# PTFV_GECKO_PWR.net
KiCad netlist of a schematic drawn in Altium Designer
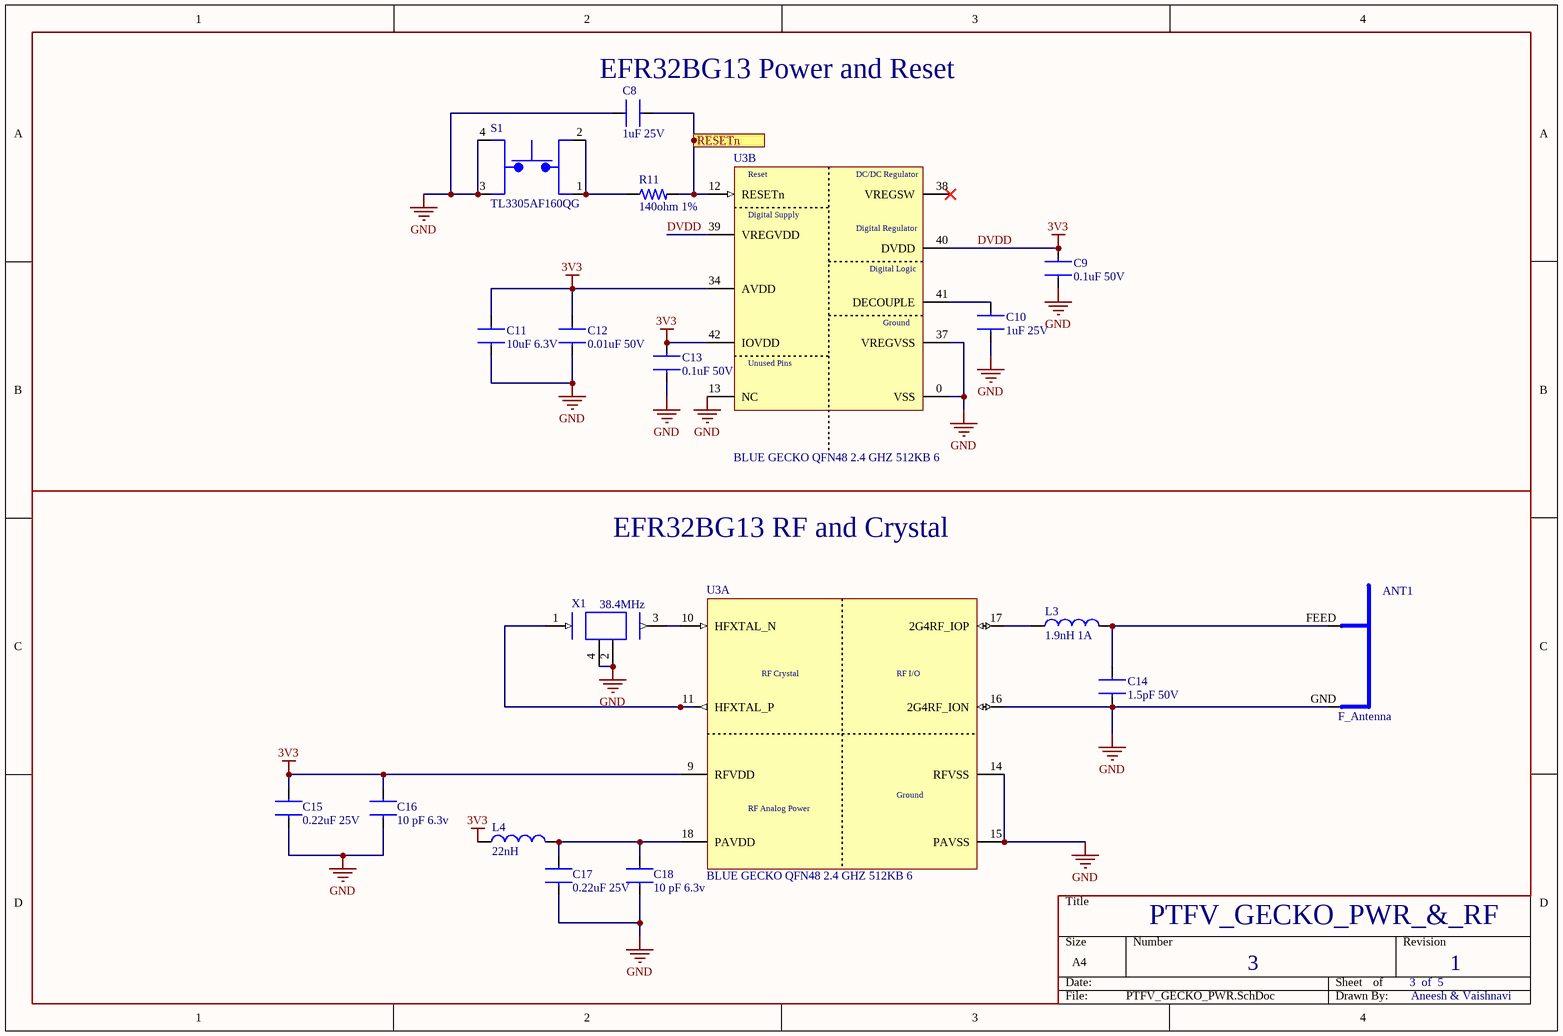
[diagram p0: PTFV_GECKO_PWR.SchDoc]

(export (version "E")
  (design (tool "Eeschema 10.0.6"))
  (components
    (comp (ref "ANT1")
      (value "F_Antenna")
      (description "Inverted F Antenna")
      (libsource (lib "LPEDT_Parts") (part "F_Antenna"))
    )
    (comp (ref "C8")
      (value "1uF 25V")
      (footprint "CAP_0603_1MM")
      (description "CAP CER 1uF 25V X5R 0603")
      (fields
        (field (name "MANUFACTURER") "Yageo")
        (field (name "MANUFACTURER PART NUMBER") "CC0603KRX5R8BB105")
      )
      (libsource (lib "LPEDT_Parts_Library") (part "CC0603KRX5R8BB105"))
    )
    (comp (ref "C9")
      (value "0.1uF 50V")
      (footprint "CAP_0603_1MM")
      (description "CAP CER 0.1UF 50V X5R 0603")
      (fields
        (field (name "MANUFACTURER") "Yageo")
        (field (name "MANUFACTURER PART NUMBER") "CC0603KRX5R9BB104")
      )
      (libsource (lib "LPEDT_Parts_Library") (part "CC0603KRX5R9BB104"))
    )
    (comp (ref "C10")
      (value "1uF 25V")
      (footprint "CAP_0603_1MM")
      (description "CAP CER 1uF 25V X5R 0603")
      (fields
        (field (name "MANUFACTURER") "Yageo")
        (field (name "MANUFACTURER PART NUMBER") "CC0603KRX5R8BB105")
      )
      (libsource (lib "LPEDT_Parts") (part "CC0603KRX5R8BB105"))
    )
    (comp (ref "C11")
      (value "10uF 6.3V")
      (footprint "CAP_0603_1MM")
      (description "CAP CER 10UF 6.3V X5R 0603")
      (fields
        (field (name "MANUFACTURER") "Samsung")
        (field (name "MANUFACTURER PART NUMBER") "CL10A106MQ8NNNC")
      )
      (libsource (lib "LPEDT_Parts_Library") (part "CL10A106MQ8NNNC"))
    )
    (comp (ref "C12")
      (value "0.01uF 50V")
      (footprint "CAP_0603_1MM")
      (description "CAP CER 0.01uF 50V X7R 0603")
      (fields
        (field (name "MANUFACTURER") "Yageo")
        (field (name "MANUFACTURER PART NUMBER") "CC0603KRX7R9BB103")
      )
      (libsource (lib "LPEDT_Parts_Library") (part "CC0603KRX7R9BB103"))
    )
    (comp (ref "C13")
      (value "0.1uF 50V")
      (footprint "CAP_0603_1MM")
      (description "CAP CER 0.1UF 50V X5R 0603")
      (fields
        (field (name "MANUFACTURER") "Yageo")
        (field (name "MANUFACTURER PART NUMBER") "CC0603KRX5R9BB104")
      )
      (libsource (lib "LPEDT_Parts_Library") (part "CC0603KRX5R9BB104"))
    )
    (comp (ref "C14")
      (value "1.5pF 50V")
      (footprint "CAP_0402_1mm")
      (description "CAP CER 1.5pF 50V C0G 5% Pad SMD 0402 125C Automotive T/R")
      (fields
        (field (name "MANUFACTURER") "Murata")
        (field (name "MANUFACTURER PART NUMBER") "GCM1555C1H1R5JA16D")
      )
      (libsource (lib "LPEDT_Parts_Library") (part "GCM1555C1H1R5JA16D"))
    )
    (comp (ref "C15")
      (value "0.22uF 25V")
      (footprint "CAP_0603_1MM")
      (description "CAP CER 0.22UF 25V X7R 0603")
      (fields
        (field (name "MANUFACTURER") "Vishay Vitramon")
        (field (name "MANUFACTURER PART NUMBER") "VJ0603Y224KXXCW1BC")
      )
      (libsource (lib "LPEDT_Parts_Library") (part "VJ0603Y224KXXCW1BC"))
    )
    (comp (ref "C16")
      (value "10 pF 6.3v")
      (footprint "CAP_0603_1MM")
      (description "CAP CER 10pF 6.3V 0603")
      (fields
        (field (name "MANUFACTURER") "Kyocera AVX")
        (field (name "MANUFACTURER PART NUMBER") "06036A100FAT2A")
      )
      (libsource (lib "LPEDT_Parts_Library") (part "06036A100FAT2A"))
    )
    (comp (ref "C17")
      (value "0.22uF 25V")
      (footprint "CAP_0603_1MM")
      (description "CAP CER 0.22UF 25V X7R 0603")
      (fields
        (field (name "MANUFACTURER") "Vishay Vitramon")
        (field (name "MANUFACTURER PART NUMBER") "VJ0603Y224KXXCW1BC")
      )
      (libsource (lib "LPEDT_Parts_Library") (part "VJ0603Y224KXXCW1BC"))
    )
    (comp (ref "C18")
      (value "10 pF 6.3v")
      (footprint "CAP_0603_1MM")
      (description "CAP CER 10pF 6.3V 0603")
      (fields
        (field (name "MANUFACTURER") "Kyocera AVX")
        (field (name "MANUFACTURER PART NUMBER") "06036A100FAT2A")
      )
      (libsource (lib "LPEDT_Parts_Library") (part "06036A100FAT2A"))
    )
    (comp (ref "L3")
      (value "1.9nH 1A")
      (footprint "CAP_0402_1mm")
      (description "Inductor Chip 1.9nH 0.3nH Tolerance 2-Pin 0402 Paper T/R")
      (fields
        (field (name "MANUFACTURER") "Murata")
        (field (name "MANUFACTURER PART NUMBER") "LQG15WZ1N9S02D")
      )
      (libsource (lib "LPEDT_Parts_Library") (part "LQG15WZ1N9S02D"))
    )
    (comp (ref "L4")
      (value "22nH")
      (footprint "IND_1608X10N")
      (description "IND CER  22nH, 1.6Ghz, 0.3A, 0603 Rohs Compliant: Yes")
      (fields
        (field (name "MANUFACTURER") "Wurth Electronics")
        (field (name "MANUFACTURER PART NUMBER") "7447860122")
      )
      (libsource (lib "LPEDT_Parts_Library") (part "7447860122"))
    )
    (comp (ref "R11")
      (value "140ohm 1%")
      (footprint "RES_0603_1608X06")
      (description "RES SMD 140 OHM 1% 1/10W 0603")
      (fields
        (field (name "MANUFACTURER") "Yageo")
        (field (name "MANUFACTURER PART NUMBER") "RC0603FR-07140RL")
      )
      (libsource (lib "LPEDT_Parts_Library") (part "RC0603FR-07140RL"))
    )
    (comp (ref "S1")
      (value "TL3305AF160QG")
      (footprint "SW_TL3305AF160QG")
      (description "Tactile Switch SPST-NO Top Actuated Surface Mount")
      (fields (field (name "MF") "E-Switch"))
      (libsource (lib "LPEDT_Parts_Library") (part "TL3305AF160QG"))
    )
    (comp (ref "U3")
      (value "BLUE GECKO QFN48 2.4 GHZ 512KB 6")
      (footprint "QFN_48_7X7")
      (description "Blue Gecko BLE Soc QFN48 2.4 G 10 dB BLE/Proprietary 512 kB 64 kB(RAM) 31GPIO")
      (fields
        (field (name "MANUFACTURER") "Silicon Labs")
        (field (name "MANUFACTURER PART NUMBER") "EFR32BG13P632F512GM48-DR")
      )
      (libsource (lib "LPEDT_Parts") (part "EFR32BG13P632F512GM48-DR"))
    )
    (comp (ref "X1")
      (value "38.4MHz")
      (footprint "OSC_38.4MHz")
      (description "Crystal 38.4000MHZ 10PF SMD")
      (fields
        (field (name "MANUFACTURER") "Raltron Electronics")
        (field (name "MANUFACTURER PART NUMBER") "RH100-38.400-10-F-1010-TR")
      )
      (libsource (lib "LPEDT_Parts_Library") (part "RH100-38.400-10-F-1010-TR"))
    )
  )
  (nets
    (net (code "1") (name "/RESETn") (class "Default")
      (node (ref "C8") (pin "1") (pinfunction "1_1") (pintype "passive"))
      (node (ref "R11") (pin "2") (pinfunction "2_2") (pintype "passive"))
      (node (ref "U3") (pin "12") (pinfunction "RESETn_12") (pintype "input"))
    )
    (net (code "2") (name "3V3") (class "Default")
      (node (ref "C11") (pin "1") (pinfunction "1_1") (pintype "passive"))
      (node (ref "C12") (pin "1") (pinfunction "1_1") (pintype "passive"))
      (node (ref "C13") (pin "1") (pinfunction "1_1") (pintype "passive"))
      (node (ref "C15") (pin "1") (pinfunction "1_1") (pintype "passive"))
      (node (ref "C16") (pin "1") (pinfunction "1_1") (pintype "passive"))
      (node (ref "C9") (pin "1") (pinfunction "1_1") (pintype "passive"))
      (node (ref "L4") (pin "1") (pinfunction "1_1") (pintype "passive"))
      (node (ref "U3") (pin "34") (pinfunction "AVDD_34") (pintype "power_in"))
      (node (ref "U3") (pin "39") (pinfunction "VREGVDD_39") (pintype "power_in"))
      (node (ref "U3") (pin "40") (pinfunction "DVDD_40") (pintype "power_in"))
      (node (ref "U3") (pin "42") (pinfunction "IOVDD_42") (pintype "power_in"))
      (node (ref "U3") (pin "9") (pinfunction "RFVDD_9") (pintype "power_in"))
    )
    (net (code "3") (name "GND") (class "Default")
      (node (ref "ANT1") (pin "GND") (pinfunction "23_GND") (pintype "passive"))
      (node (ref "C10") (pin "2") (pinfunction "2_2") (pintype "passive"))
      (node (ref "C11") (pin "2") (pinfunction "2_2") (pintype "passive"))
      (node (ref "C12") (pin "2") (pinfunction "2_2") (pintype "passive"))
      (node (ref "C13") (pin "2") (pinfunction "2_2") (pintype "passive"))
      (node (ref "C14") (pin "2") (pinfunction "2_2") (pintype "passive"))
      (node (ref "C15") (pin "2") (pinfunction "2_2") (pintype "passive"))
      (node (ref "C16") (pin "2") (pinfunction "2_2") (pintype "passive"))
      (node (ref "C17") (pin "2") (pinfunction "2_2") (pintype "passive"))
      (node (ref "C18") (pin "2") (pinfunction "2_2") (pintype "passive"))
      (node (ref "C8") (pin "2") (pinfunction "2_2") (pintype "passive"))
      (node (ref "C9") (pin "2") (pinfunction "2_2") (pintype "passive"))
      (node (ref "S1") (pin "3") (pinfunction "3_3") (pintype "passive"))
      (node (ref "S1") (pin "4") (pinfunction "4_4") (pintype "passive"))
      (node (ref "U3") (pin "0") (pinfunction "VSS_0") (pintype "power_in"))
      (node (ref "U3") (pin "13") (pinfunction "NC_13") (pintype "passive"))
      (node (ref "U3") (pin "14") (pinfunction "RFVSS_14") (pintype "power_in"))
      (node (ref "U3") (pin "15") (pinfunction "PAVSS_15") (pintype "power_in"))
      (node (ref "U3") (pin "16") (pinfunction "2G4RF_ION_16") (pintype "bidirectional"))
      (node (ref "U3") (pin "37") (pinfunction "VREGVSS_37") (pintype "power_in"))
      (node (ref "X1") (pin "2") (pintype "power_in"))
      (node (ref "X1") (pin "4") (pintype "power_in"))
    )
    (net (code "4") (name "Net-(ANT1-23-PadFEED)") (class "Default")
      (node (ref "ANT1") (pin "FEED") (pinfunction "23_FEED") (pintype "passive"))
      (node (ref "C14") (pin "1") (pinfunction "1_1") (pintype "passive"))
      (node (ref "L3") (pin "2") (pinfunction "2_2") (pintype "passive"))
    )
    (net (code "5") (name "Net-(R11-Pad1)") (class "Default")
      (node (ref "R11") (pin "1") (pinfunction "1_1") (pintype "passive"))
      (node (ref "S1") (pin "1") (pinfunction "1_1") (pintype "passive"))
      (node (ref "S1") (pin "2") (pinfunction "2_2") (pintype "passive"))
    )
    (net (code "6") (name "Net-(U3A-2G4RF_IOP)") (class "Default")
      (node (ref "L3") (pin "1") (pinfunction "1_1") (pintype "passive"))
      (node (ref "U3") (pin "17") (pinfunction "2G4RF_IOP_17") (pintype "bidirectional"))
    )
    (net (code "7") (name "Net-(U3A-HFXTAL_N)") (class "Default")
      (node (ref "U3") (pin "10") (pinfunction "HFXTAL_N_10") (pintype "input"))
      (node (ref "X1") (pin "3") (pintype "output"))
    )
    (net (code "8") (name "Net-(U3A-HFXTAL_P)") (class "Default")
      (node (ref "U3") (pin "11") (pinfunction "HFXTAL_P_11") (pintype "output"))
      (node (ref "X1") (pin "1") (pintype "input"))
    )
    (net (code "9") (name "Net-(U3A-PAVDD)") (class "Default")
      (node (ref "C17") (pin "1") (pinfunction "1_1") (pintype "passive"))
      (node (ref "C18") (pin "1") (pinfunction "1_1") (pintype "passive"))
      (node (ref "L4") (pin "2") (pinfunction "2_2") (pintype "passive"))
      (node (ref "U3") (pin "18") (pinfunction "PAVDD_18") (pintype "power_in"))
    )
    (net (code "10") (name "Net-(U3B-DECOUPLE)") (class "Default")
      (node (ref "C10") (pin "1") (pinfunction "1_1") (pintype "passive"))
      (node (ref "U3") (pin "41") (pinfunction "DECOUPLE_41") (pintype "power_in"))
    )
    (net (code "11") (name "unconnected-(U3B-VREGSW-Pad38)") (class "Default")
      (node (ref "U3") (pin "38") (pinfunction "VREGSW_38") (pintype "power_in+no_connect"))
    )
  )
)
